# observer.net
KiCad netlist of a schematic drawn in EAGLE
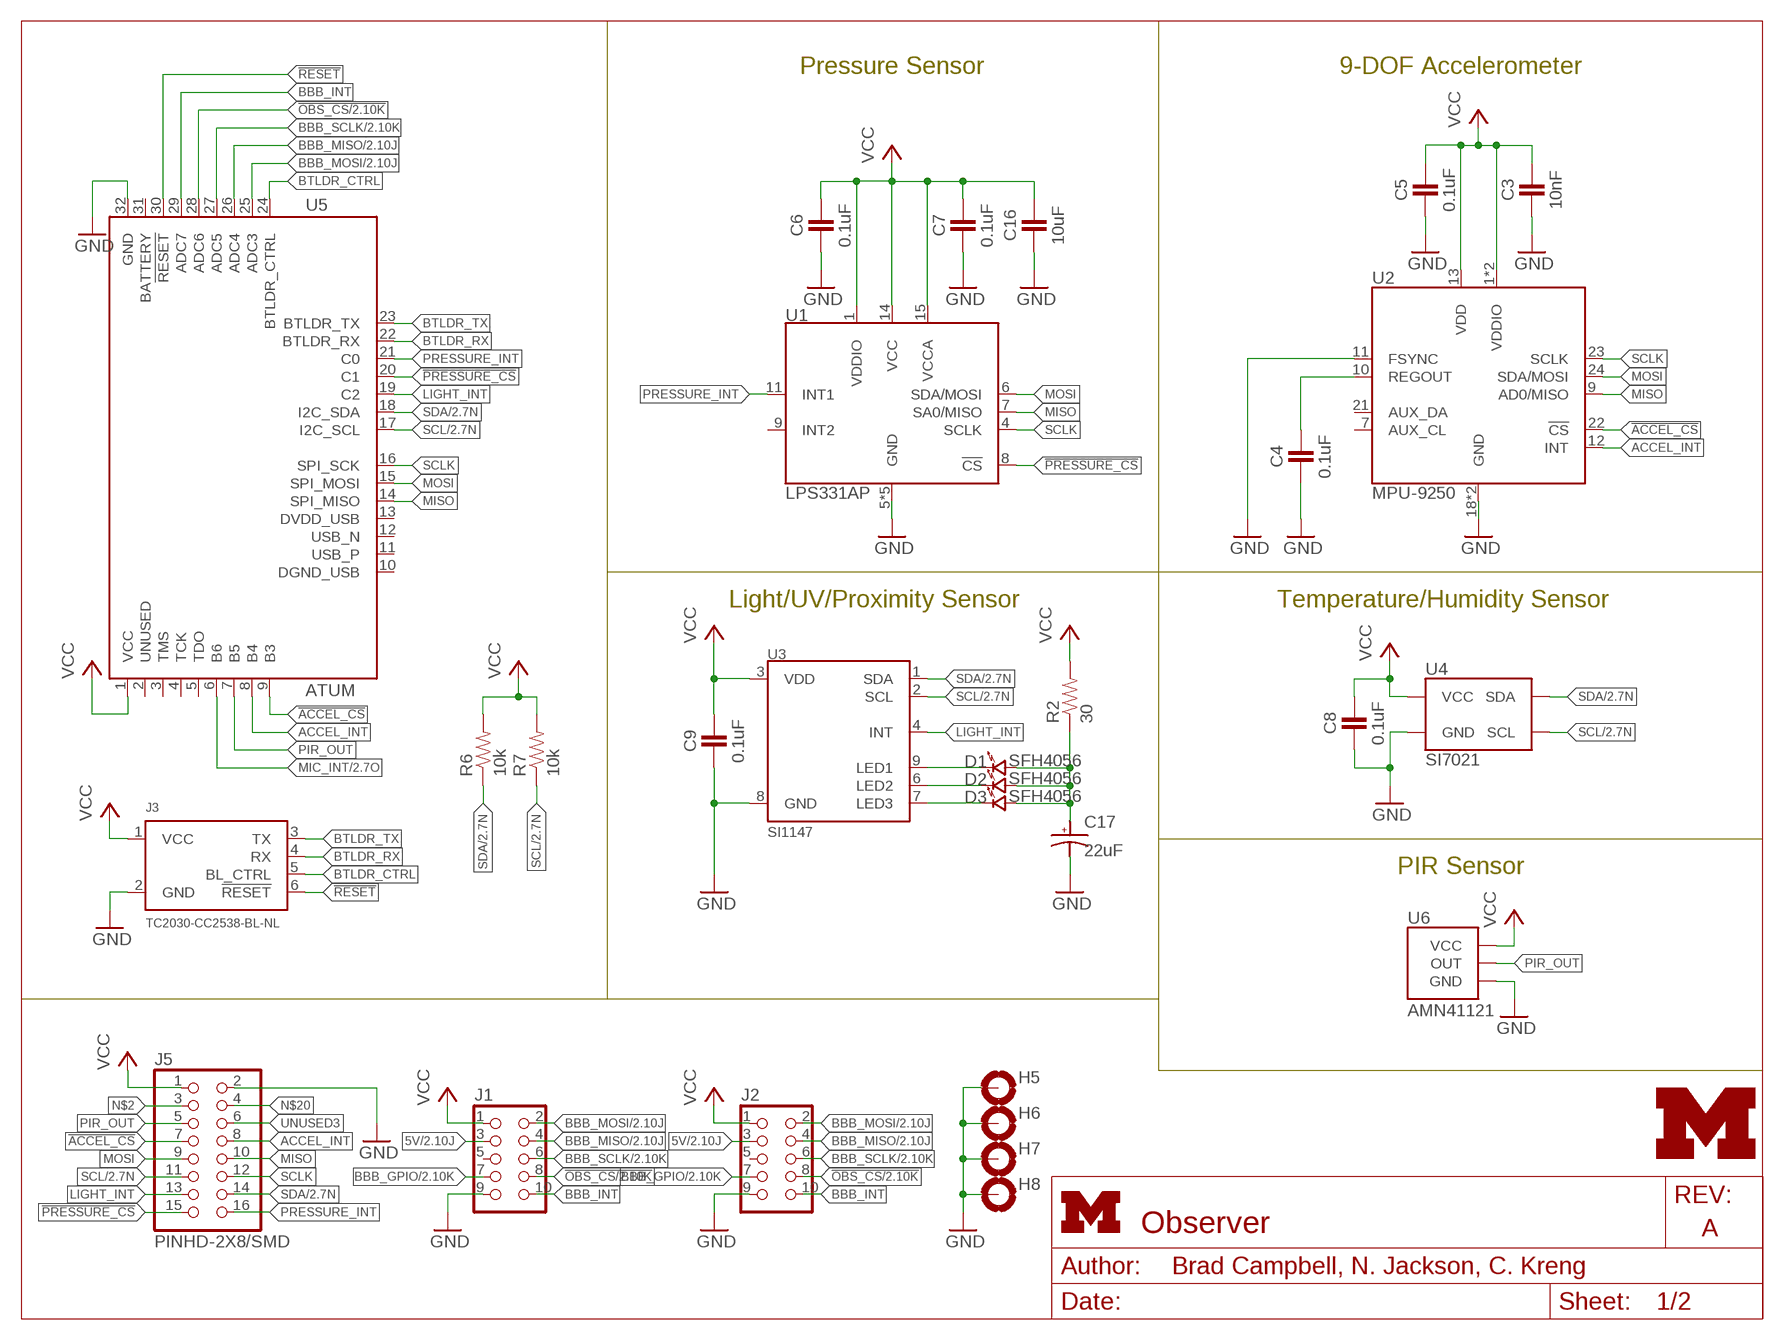
[diagram p0: schematic, sheet 1]
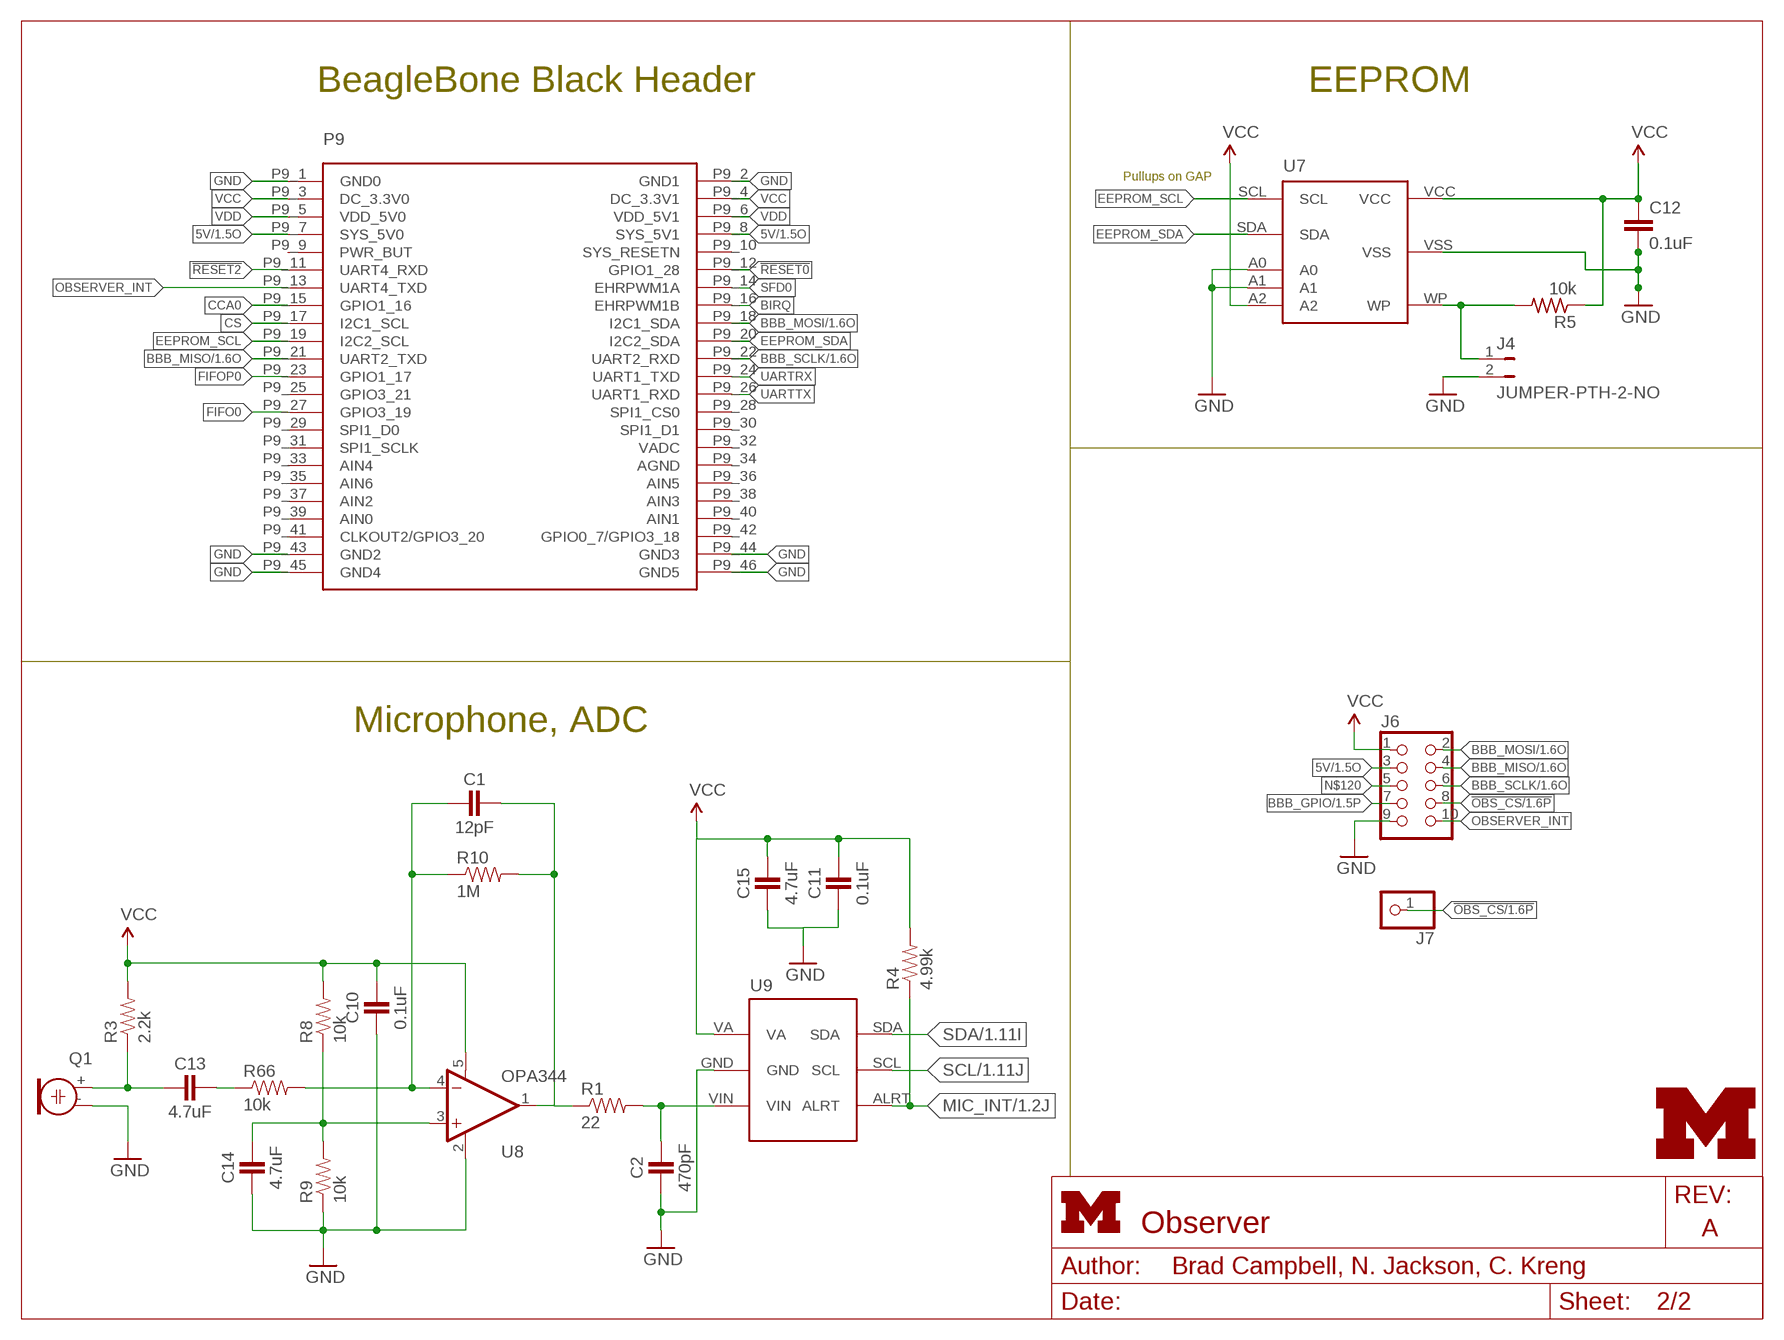
[diagram p1: schematic, sheet 2]

(export (version "E")
  (design (tool "Eeschema 10.0.6"))
  (components
    (comp (ref "C1")
      (value "12pF")
      (footprint "eagle-import:0402_CAP")
      (libsource (lib "eagle-import") (part "CAPACITOR"))
    )
    (comp (ref "C2")
      (value "470pF")
      (footprint "eagle-import:0402_CAP")
      (libsource (lib "eagle-import") (part "CAPACITOR"))
    )
    (comp (ref "C10")
      (value "0.1uF")
      (footprint "eagle-import:0402_CAP")
      (libsource (lib "eagle-import") (part "CAPACITOR"))
    )
    (comp (ref "C11")
      (value "0.1uF")
      (footprint "eagle-import:0402_CAP")
      (libsource (lib "eagle-import") (part "CAPACITOR"))
    )
    (comp (ref "C12")
      (value "0.1uF")
      (footprint "eagle-import:C0402")
      (libsource (lib "eagle-import") (part "C-EUC0402"))
    )
    (comp (ref "C13")
      (value "4.7uF")
      (footprint "eagle-import:0402_CAP")
      (libsource (lib "eagle-import") (part "CAPACITOR"))
    )
    (comp (ref "C14")
      (value "4.7uF")
      (footprint "eagle-import:0402_CAP")
      (libsource (lib "eagle-import") (part "CAPACITOR"))
    )
    (comp (ref "C15")
      (value "4.7uF")
      (footprint "eagle-import:0402_CAP")
      (libsource (lib "eagle-import") (part "CAPACITOR"))
    )
    (comp (ref "J4")
      (value "JUMPER-PTH-2-NO")
      (footprint "eagle-import:PTH-JUMPER-2-NO_NO_SILK")
      (libsource (lib "eagle-import") (part "JUMPER-PTH-2-NO"))
    )
    (comp (ref "J6")
      (value "CON_HEADER_2X05-PTH+SHROUDED_A")
      (footprint "eagle-import:PINSHRD_PTH_2X05")
      (libsource (lib "eagle-import") (part "CON_HEADER_2X05-PTH+SHROUDED_A"))
    )
    (comp (ref "J7")
      (value "PINHD-1X1")
      (footprint "eagle-import:1X01")
      (libsource (lib "eagle-import") (part "PINHD-1X1"))
    )
    (comp (ref "LOGO2")
      (value "UMICH_SOLID_TINY")
      (footprint "eagle-import:UMICH_SOLID_50MIL")
      (libsource (lib "eagle-import") (part "UMICH_SOLID_TINY"))
    )
    (comp (ref "P9/P8")
      (value "BBB_HEADER")
      (footprint "eagle-import:BBB_HEADERS")
      (libsource (lib "eagle-import") (part "BBB_HEADER"))
    )
    (comp (ref "Q1")
      (value "ELECTRET")
      (footprint "eagle-import:ELECTRET_9.7")
      (libsource (lib "eagle-import") (part "ELECTRET"))
    )
    (comp (ref "R1")
      (value "22")
      (footprint "eagle-import:0402_RES")
      (libsource (lib "eagle-import") (part "RESISTOR0402_RES"))
    )
    (comp (ref "R3")
      (value "2.2k")
      (footprint "eagle-import:0402_RES")
      (libsource (lib "eagle-import") (part "RESISTOR0402_RES"))
    )
    (comp (ref "R4")
      (value "4.99k")
      (footprint "eagle-import:0402_RES")
      (libsource (lib "eagle-import") (part "RESISTOR0402_RES"))
    )
    (comp (ref "R5")
      (value "10k")
      (footprint "eagle-import:R0402")
      (libsource (lib "eagle-import") (part "R-US_R0402"))
    )
    (comp (ref "R8")
      (value "10k")
      (footprint "eagle-import:0402_RES")
      (libsource (lib "eagle-import") (part "RESISTOR0402_RES"))
    )
    (comp (ref "R9")
      (value "10k")
      (footprint "eagle-import:0402_RES")
      (libsource (lib "eagle-import") (part "RESISTOR0402_RES"))
    )
    (comp (ref "R10")
      (value "1M")
      (footprint "eagle-import:0402_RES")
      (libsource (lib "eagle-import") (part "RESISTOR0402_RES"))
    )
    (comp (ref "R66")
      (value "10k")
      (footprint "eagle-import:0402_RES")
      (libsource (lib "eagle-import") (part "RESISTOR0402_RES"))
    )
    (comp (ref "U7")
      (value "CAT24C256WI-GT3")
      (footprint "eagle-import:CAT24C256WI-GT3")
      (libsource (lib "eagle-import") (part "CAT24C256WI-GT3"))
    )
    (comp (ref "U8")
      (value "OPA344")
      (footprint "eagle-import:SOT23-5")
      (libsource (lib "eagle-import") (part "OPA344"))
    )
    (comp (ref "U9")
      (value "ADC121C021")
      (footprint "eagle-import:ADC121C021")
      (libsource (lib "eagle-import") (part "ADC121C021"))
    )
    (comp (ref "C3")
      (value "10nF")
      (footprint "eagle-import:0402_CAP")
      (libsource (lib "eagle-import") (part "CAPACITOR"))
    )
    (comp (ref "C4")
      (value "0.1uF")
      (footprint "eagle-import:0402_CAP")
      (libsource (lib "eagle-import") (part "CAPACITOR"))
    )
    (comp (ref "C5")
      (value "0.1uF")
      (footprint "eagle-import:0402_CAP")
      (libsource (lib "eagle-import") (part "CAPACITOR"))
    )
    (comp (ref "C6")
      (value "0.1uF")
      (footprint "eagle-import:0402_CAP")
      (libsource (lib "eagle-import") (part "CAPACITOR"))
    )
    (comp (ref "C7")
      (value "0.1uF")
      (footprint "eagle-import:0402_CAP")
      (libsource (lib "eagle-import") (part "CAPACITOR"))
    )
    (comp (ref "C8")
      (value "0.1uF")
      (footprint "eagle-import:0402_CAP")
      (libsource (lib "eagle-import") (part "CAPACITOR"))
    )
    (comp (ref "C9")
      (value "0.1uF")
      (footprint "eagle-import:0402_CAP")
      (libsource (lib "eagle-import") (part "CAPACITOR"))
    )
    (comp (ref "C16")
      (value "10uF")
      (footprint "eagle-import:0402_CAP")
      (libsource (lib "eagle-import") (part "CAPACITOR"))
    )
    (comp (ref "C17")
      (value "22uF")
      (footprint "eagle-import:CAP0603")
      (libsource (lib "eagle-import") (part "CAP_POL0603"))
    )
    (comp (ref "D1")
      (value "SFH4056")
      (footprint "eagle-import:SFH4056")
      (libsource (lib "eagle-import") (part "SFH4056"))
    )
    (comp (ref "D2")
      (value "SFH4056")
      (footprint "eagle-import:SFH4056")
      (libsource (lib "eagle-import") (part "SFH4056"))
    )
    (comp (ref "D3")
      (value "SFH4056")
      (footprint "eagle-import:SFH4056")
      (libsource (lib "eagle-import") (part "SFH4056"))
    )
    (comp (ref "H5")
      (value "MOUNT-PAD-ROUND3.2")
      (footprint "eagle-import:3,2-PAD")
      (libsource (lib "eagle-import") (part "MOUNT-PAD-ROUND3.2"))
    )
    (comp (ref "H6")
      (value "MOUNT-PAD-ROUND3.2")
      (footprint "eagle-import:3,2-PAD")
      (libsource (lib "eagle-import") (part "MOUNT-PAD-ROUND3.2"))
    )
    (comp (ref "H7")
      (value "MOUNT-PAD-ROUND3.2")
      (footprint "eagle-import:3,2-PAD")
      (libsource (lib "eagle-import") (part "MOUNT-PAD-ROUND3.2"))
    )
    (comp (ref "H8")
      (value "MOUNT-PAD-ROUND3.2")
      (footprint "eagle-import:3,2-PAD")
      (libsource (lib "eagle-import") (part "MOUNT-PAD-ROUND3.2"))
    )
    (comp (ref "J1")
      (value "CON_HEADER_2X05-SMD+SHROUDED")
      (footprint "eagle-import:PINSHRD_SMT_2X05")
      (libsource (lib "eagle-import") (part "CON_HEADER_2X05-SMD+SHROUDED"))
    )
    (comp (ref "J2")
      (value "CON_HEADER_2X05-SMD+SHROUDED")
      (footprint "eagle-import:PINSHRD_SMT_2X05")
      (libsource (lib "eagle-import") (part "CON_HEADER_2X05-SMD+SHROUDED"))
    )
    (comp (ref "J3")
      (value "TC2030-CC2538-BL-NL")
      (footprint "eagle-import:TC2030-IDC-NL")
      (libsource (lib "eagle-import") (part "TC2030-CC2538-BL-NL"))
    )
    (comp (ref "J5")
      (value "PINHD-2X8/SMD")
      (footprint "eagle-import:2X8_SMD")
      (libsource (lib "eagle-import") (part "PINHD-2X8/SMD"))
    )
    (comp (ref "LOGO1")
      (value "UMICH_SOLID_TINY")
      (footprint "eagle-import:UMICH_SOLID_50MIL")
      (libsource (lib "eagle-import") (part "UMICH_SOLID_TINY"))
    )
    (comp (ref "R2")
      (value "30")
      (footprint "eagle-import:0402_RES")
      (libsource (lib "eagle-import") (part "RESISTOR0402_RES"))
    )
    (comp (ref "R6")
      (value "10k")
      (footprint "eagle-import:0402_RES")
      (libsource (lib "eagle-import") (part "RESISTOR0402_RES"))
    )
    (comp (ref "R7")
      (value "10k")
      (footprint "eagle-import:0402_RES")
      (libsource (lib "eagle-import") (part "RESISTOR0402_RES"))
    )
    (comp (ref "U1")
      (value "LPS331AP")
      (footprint "eagle-import:HCLGA-16_3MM")
      (libsource (lib "eagle-import") (part "LPS331AP"))
    )
    (comp (ref "U2")
      (value "MPU-9250")
      (footprint "eagle-import:QFN-24_3MM")
      (libsource (lib "eagle-import") (part "MPU-9250"))
    )
    (comp (ref "U3")
      (value "SI1147")
      (footprint "eagle-import:QFN-10_2MM")
      (libsource (lib "eagle-import") (part "SI1147"))
    )
    (comp (ref "U4")
      (value "SI7021")
      (footprint "eagle-import:DFN-6_3MM")
      (libsource (lib "eagle-import") (part "SI7021"))
    )
    (comp (ref "U5")
      (value "ATUM")
      (footprint "eagle-import:ATUM")
      (libsource (lib "eagle-import") (part "ATUM"))
    )
    (comp (ref "U6")
      (value "AMN41121")
      (footprint "eagle-import:AMN2")
      (libsource (lib "eagle-import") (part "AMN41121"))
    )
  )
  (nets
    (net (code "1") (name "5V") (class "Default")
      (node (ref "J1") (pin "3") (pinfunction "3_3") (pintype "passive"))
      (node (ref "J2") (pin "3") (pinfunction "3_3") (pintype "passive"))
      (node (ref "J6") (pin "3") (pinfunction "3_3") (pintype "passive"))
      (node (ref "P9/P8") (pin "P9_7") (pinfunction "SYS_5V0_P9_7") (pintype "bidirectional"))
      (node (ref "P9/P8") (pin "P9_8") (pinfunction "SYS_5V1_P9_8") (pintype "bidirectional"))
    )
    (net (code "2") (name "ACCEL_INT") (class "Default")
      (node (ref "J5") (pin "8") (pinfunction "8_8") (pintype "passive"))
      (node (ref "U2") (pin "12") (pinfunction "INT_12") (pintype "bidirectional"))
      (node (ref "U5") (pin "8") (pinfunction "B4_8") (pintype "bidirectional"))
    )
    (net (code "3") (name "BBB_GPIO") (class "Default")
      (node (ref "J1") (pin "7") (pinfunction "7_7") (pintype "passive"))
      (node (ref "J2") (pin "7") (pinfunction "7_7") (pintype "passive"))
      (node (ref "J6") (pin "7") (pinfunction "7_7") (pintype "passive"))
    )
    (net (code "4") (name "BBB_INT") (class "Default")
      (node (ref "J1") (pin "10") (pinfunction "10_10") (pintype "passive"))
      (node (ref "J2") (pin "10") (pinfunction "10_10") (pintype "passive"))
      (node (ref "U5") (pin "29") (pinfunction "ADC7_29") (pintype "bidirectional"))
    )
    (net (code "5") (name "BBB_MISO") (class "Default")
      (node (ref "J1") (pin "4") (pinfunction "4_4") (pintype "passive"))
      (node (ref "J2") (pin "4") (pinfunction "4_4") (pintype "passive"))
      (node (ref "J6") (pin "4") (pinfunction "4_4") (pintype "passive"))
      (node (ref "P9/P8") (pin "P9_21") (pinfunction "UART2_TXD_P9_21") (pintype "bidirectional"))
      (node (ref "U5") (pin "26") (pinfunction "ADC4_26") (pintype "bidirectional"))
    )
    (net (code "6") (name "BBB_MOSI") (class "Default")
      (node (ref "J1") (pin "2") (pinfunction "2_2") (pintype "passive"))
      (node (ref "J2") (pin "2") (pinfunction "2_2") (pintype "passive"))
      (node (ref "J6") (pin "2") (pinfunction "2_2") (pintype "passive"))
      (node (ref "P9/P8") (pin "P9_18") (pinfunction "I2C1_SDA_P9_18") (pintype "bidirectional"))
      (node (ref "U5") (pin "25") (pinfunction "ADC3_25") (pintype "bidirectional"))
    )
    (net (code "7") (name "BBB_SCLK") (class "Default")
      (node (ref "J1") (pin "6") (pinfunction "6_6") (pintype "passive"))
      (node (ref "J2") (pin "6") (pinfunction "6_6") (pintype "passive"))
      (node (ref "J6") (pin "6") (pinfunction "6_6") (pintype "passive"))
      (node (ref "P9/P8") (pin "P9_22") (pinfunction "UART2_RXD_P9_22") (pintype "bidirectional"))
      (node (ref "U5") (pin "27") (pinfunction "ADC5_27") (pintype "bidirectional"))
    )
    (net (code "8") (name "BIRQ") (class "Default")
      (node (ref "P9/P8") (pin "P9_16") (pinfunction "EHRPWM1B_P9_16") (pintype "bidirectional"))
    )
    (net (code "9") (name "BTLDR_CTRL") (class "Default")
      (node (ref "J3") (pin "5") (pinfunction "BL_CTRL_5") (pintype "bidirectional"))
      (node (ref "U5") (pin "24") (pinfunction "BTLDR_CTRL_24") (pintype "bidirectional"))
    )
    (net (code "10") (name "BTLDR_RX") (class "Default")
      (node (ref "J3") (pin "4") (pinfunction "RX_4") (pintype "bidirectional"))
      (node (ref "U5") (pin "22") (pinfunction "BTLDR_RX_22") (pintype "bidirectional"))
    )
    (net (code "11") (name "BTLDR_TX") (class "Default")
      (node (ref "J3") (pin "3") (pinfunction "TX_3") (pintype "bidirectional"))
      (node (ref "U5") (pin "23") (pinfunction "BTLDR_TX_23") (pintype "bidirectional"))
    )
    (net (code "12") (name "CCA0") (class "Default")
      (node (ref "P9/P8") (pin "P9_15") (pinfunction "GPIO1_16_P9_15") (pintype "bidirectional"))
    )
    (net (code "13") (name "CS") (class "Default")
      (node (ref "P9/P8") (pin "P9_17") (pinfunction "I2C1_SCL_P9_17") (pintype "bidirectional"))
    )
    (net (code "14") (name "EEPROM_SCL") (class "Default")
      (node (ref "P9/P8") (pin "P9_19") (pinfunction "I2C2_SCL_P9_19") (pintype "bidirectional"))
      (node (ref "U7") (pin "SCL") (pinfunction "SCL_SCL") (pintype "bidirectional"))
    )
    (net (code "15") (name "EEPROM_SDA") (class "Default")
      (node (ref "P9/P8") (pin "P9_20") (pinfunction "I2C2_SDA_P9_20") (pintype "bidirectional"))
      (node (ref "U7") (pin "SDA") (pinfunction "SDA_SDA") (pintype "bidirectional"))
    )
    (net (code "16") (name "FIFO0") (class "Default")
      (node (ref "P9/P8") (pin "P9_27") (pinfunction "GPIO3_19_P9_27") (pintype "bidirectional"))
    )
    (net (code "17") (name "FIFOP0") (class "Default")
      (node (ref "P9/P8") (pin "P9_23") (pinfunction "GPIO1_17_P9_23") (pintype "bidirectional"))
    )
    (net (code "18") (name "GND") (class "Default")
      (node (ref "C10") (pin "2") (pinfunction "2_2") (pintype "bidirectional"))
      (node (ref "C11") (pin "2") (pinfunction "2_2") (pintype "bidirectional"))
      (node (ref "C12") (pin "2") (pinfunction "2_2") (pintype "passive"))
      (node (ref "C14") (pin "2") (pinfunction "2_2") (pintype "bidirectional"))
      (node (ref "C15") (pin "2") (pinfunction "2_2") (pintype "bidirectional"))
      (node (ref "C16") (pin "2") (pinfunction "2_2") (pintype "bidirectional"))
      (node (ref "C17") (pin "NEG") (pinfunction "ANODE_NEG") (pintype "bidirectional"))
      (node (ref "C2") (pin "2") (pinfunction "2_2") (pintype "bidirectional"))
      (node (ref "C3") (pin "2") (pinfunction "2_2") (pintype "bidirectional"))
      (node (ref "C4") (pin "2") (pinfunction "2_2") (pintype "bidirectional"))
      (node (ref "C5") (pin "2") (pinfunction "2_2") (pintype "bidirectional"))
      (node (ref "C6") (pin "2") (pinfunction "2_2") (pintype "bidirectional"))
      (node (ref "C7") (pin "2") (pinfunction "2_2") (pintype "bidirectional"))
      (node (ref "C8") (pin "2") (pinfunction "2_2") (pintype "bidirectional"))
      (node (ref "C9") (pin "2") (pinfunction "2_2") (pintype "bidirectional"))
      (node (ref "H5") (pin "B3,2") (pinfunction "MOUNT_B3,2") (pintype "passive"))
      (node (ref "H6") (pin "B3,2") (pinfunction "MOUNT_B3,2") (pintype "passive"))
      (node (ref "H7") (pin "B3,2") (pinfunction "MOUNT_B3,2") (pintype "passive"))
      (node (ref "H8") (pin "B3,2") (pinfunction "MOUNT_B3,2") (pintype "passive"))
      (node (ref "J1") (pin "9") (pinfunction "9_9") (pintype "passive"))
      (node (ref "J2") (pin "9") (pinfunction "9_9") (pintype "passive"))
      (node (ref "J3") (pin "2") (pinfunction "GND_2") (pintype "bidirectional"))
      (node (ref "J4") (pin "2") (pinfunction "2_2") (pintype "passive"))
      (node (ref "J5") (pin "2") (pinfunction "2_2") (pintype "passive"))
      (node (ref "J6") (pin "9") (pinfunction "9_9") (pintype "passive"))
      (node (ref "P9/P8") (pin "P9_1") (pinfunction "GND0_P9_1") (pintype "bidirectional"))
      (node (ref "P9/P8") (pin "P9_2") (pinfunction "GND1_P9_2") (pintype "bidirectional"))
      (node (ref "P9/P8") (pin "P9_43") (pinfunction "GND2_P9_43") (pintype "bidirectional"))
      (node (ref "P9/P8") (pin "P9_44") (pinfunction "GND3_P9_44") (pintype "bidirectional"))
      (node (ref "P9/P8") (pin "P9_45") (pinfunction "GND4_P9_45") (pintype "bidirectional"))
      (node (ref "P9/P8") (pin "P9_46") (pinfunction "GND5_P9_46") (pintype "bidirectional"))
      (node (ref "Q1") (pin "-") (pinfunction "1_-") (pintype "passive"))
      (node (ref "R9") (pin "1") (pinfunction "1_1") (pintype "passive"))
      (node (ref "U1") (pin "10") (pinfunction "GND_10") (pintype "bidirectional"))
      (node (ref "U1") (pin "12") (pinfunction "GND_12") (pintype "bidirectional"))
      (node (ref "U1") (pin "13") (pinfunction "GND_13") (pintype "bidirectional"))
      (node (ref "U1") (pin "16") (pinfunction "GND_16") (pintype "bidirectional"))
      (node (ref "U1") (pin "5") (pinfunction "GND_5") (pintype "bidirectional"))
      (node (ref "U2") (pin "11") (pinfunction "FSYNC_11") (pintype "bidirectional"))
      (node (ref "U2") (pin "18") (pinfunction "GND_18") (pintype "bidirectional"))
      (node (ref "U2") (pin "20") (pinfunction "GND_20") (pintype "bidirectional"))
      (node (ref "U3") (pin "8") (pinfunction "GND_8") (pintype "bidirectional"))
      (node (ref "U4") (pin "2") (pinfunction "GND_2") (pintype "bidirectional"))
      (node (ref "U5") (pin "32") (pinfunction "GND_32") (pintype "bidirectional"))
      (node (ref "U6") (pin "GND") (pinfunction "GND_GND") (pintype "bidirectional"))
      (node (ref "U7") (pin "A0") (pinfunction "A0_A0") (pintype "bidirectional"))
      (node (ref "U7") (pin "A1") (pinfunction "A1_A1") (pintype "bidirectional"))
      (node (ref "U7") (pin "VSS") (pinfunction "VSS_VSS") (pintype "bidirectional"))
      (node (ref "U8") (pin "2") (pinfunction "V-_2") (pintype "power_in"))
      (node (ref "U9") (pin "GND") (pinfunction "GND_GND") (pintype "bidirectional"))
    )
    (net (code "19") (name "LIGHT_INT") (class "Default")
      (node (ref "J5") (pin "13") (pinfunction "13_13") (pintype "passive"))
      (node (ref "U3") (pin "4") (pinfunction "INT_4") (pintype "bidirectional"))
      (node (ref "U5") (pin "19") (pinfunction "C2_19") (pintype "bidirectional"))
    )
    (net (code "20") (name "MIC_INT") (class "Default")
      (node (ref "R4") (pin "1") (pinfunction "1_1") (pintype "passive"))
      (node (ref "U5") (pin "6") (pinfunction "B6_6") (pintype "bidirectional"))
      (node (ref "U9") (pin "ALRT") (pinfunction "ALRT_ALRT") (pintype "bidirectional"))
    )
    (net (code "21") (name "MISO") (class "Default")
      (node (ref "J5") (pin "10") (pinfunction "10_10") (pintype "passive"))
      (node (ref "U1") (pin "7") (pinfunction "SA0/MISO_7") (pintype "bidirectional"))
      (node (ref "U2") (pin "9") (pinfunction "AD0/MISO_9") (pintype "bidirectional"))
      (node (ref "U5") (pin "14") (pinfunction "SPI_MISO_14") (pintype "bidirectional"))
    )
    (net (code "22") (name "MOSI") (class "Default")
      (node (ref "J5") (pin "9") (pinfunction "9_9") (pintype "passive"))
      (node (ref "U1") (pin "6") (pinfunction "SDA/MOSI_6") (pintype "bidirectional"))
      (node (ref "U2") (pin "24") (pinfunction "SDA/MOSI_24") (pintype "bidirectional"))
      (node (ref "U5") (pin "15") (pinfunction "SPI_MOSI_15") (pintype "bidirectional"))
    )
    (net (code "23") (name "N$2") (class "Default")
      (node (ref "J5") (pin "3") (pinfunction "3_3") (pintype "passive"))
    )
    (net (code "24") (name "N$20") (class "Default")
      (node (ref "J5") (pin "4") (pinfunction "4_4") (pintype "passive"))
    )
    (net (code "25") (name "N$120") (class "Default")
      (node (ref "J6") (pin "5") (pinfunction "5_5") (pintype "passive"))
    )
    (net (code "26") (name "Net-(C2-Pad1)") (class "Default")
      (node (ref "C2") (pin "1") (pinfunction "1_1") (pintype "bidirectional"))
      (node (ref "R1") (pin "2") (pinfunction "2_2") (pintype "passive"))
      (node (ref "U9") (pin "VIN") (pinfunction "VIN_VIN") (pintype "bidirectional"))
    )
    (net (code "27") (name "Net-(C13-Pad1)") (class "Default")
      (node (ref "C13") (pin "1") (pinfunction "1_1") (pintype "bidirectional"))
      (node (ref "R66") (pin "1") (pinfunction "1_1") (pintype "passive"))
    )
    (net (code "28") (name "Net-(C17-CATHODE)") (class "Default")
      (node (ref "C17") (pin "POS") (pinfunction "CATHODE_POS") (pintype "bidirectional"))
      (node (ref "D1") (pin "ANODE") (pinfunction "ANODE_ANODE") (pintype "bidirectional"))
      (node (ref "D2") (pin "ANODE") (pinfunction "ANODE_ANODE") (pintype "bidirectional"))
      (node (ref "D3") (pin "ANODE") (pinfunction "ANODE_ANODE") (pintype "bidirectional"))
      (node (ref "R2") (pin "1") (pinfunction "1_1") (pintype "passive"))
    )
    (net (code "29") (name "Net-(J4-Pad1)") (class "Default")
      (node (ref "J4") (pin "1") (pinfunction "1_1") (pintype "passive"))
      (node (ref "R5") (pin "2") (pinfunction "2_2") (pintype "passive"))
      (node (ref "U7") (pin "WP") (pinfunction "WP_WP") (pintype "bidirectional"))
    )
    (net (code "30") (name "Net-(Q1-2)") (class "Default")
      (node (ref "C13") (pin "2") (pinfunction "2_2") (pintype "bidirectional"))
      (node (ref "Q1") (pin "+") (pinfunction "2_+") (pintype "passive"))
      (node (ref "R3") (pin "1") (pinfunction "1_1") (pintype "passive"))
    )
    (net (code "31") (name "Net-(U2-REGOUT)") (class "Default")
      (node (ref "C4") (pin "1") (pinfunction "1_1") (pintype "bidirectional"))
      (node (ref "U2") (pin "10") (pinfunction "REGOUT_10") (pintype "bidirectional"))
    )
    (net (code "32") (name "Net-(U3-LED1)") (class "Default")
      (node (ref "D1") (pin "CATHODE") (pinfunction "CATHODE_CATHODE") (pintype "bidirectional"))
      (node (ref "U3") (pin "9") (pinfunction "LED1_9") (pintype "bidirectional"))
    )
    (net (code "33") (name "Net-(U3-LED2)") (class "Default")
      (node (ref "D2") (pin "CATHODE") (pinfunction "CATHODE_CATHODE") (pintype "bidirectional"))
      (node (ref "U3") (pin "6") (pinfunction "LED2_6") (pintype "bidirectional"))
    )
    (net (code "34") (name "Net-(U3-LED3)") (class "Default")
      (node (ref "D3") (pin "CATHODE") (pinfunction "CATHODE_CATHODE") (pintype "bidirectional"))
      (node (ref "U3") (pin "7") (pinfunction "LED3_7") (pintype "bidirectional"))
    )
    (net (code "35") (name "Net-(U8-+IN)") (class "Default")
      (node (ref "C14") (pin "1") (pinfunction "1_1") (pintype "bidirectional"))
      (node (ref "R8") (pin "1") (pinfunction "1_1") (pintype "passive"))
      (node (ref "R9") (pin "2") (pinfunction "2_2") (pintype "passive"))
      (node (ref "U8") (pin "3") (pinfunction "+IN_3") (pintype "input"))
    )
    (net (code "36") (name "Net-(U8--IN)") (class "Default")
      (node (ref "C1") (pin "2") (pinfunction "2_2") (pintype "bidirectional"))
      (node (ref "R10") (pin "1") (pinfunction "1_1") (pintype "passive"))
      (node (ref "R66") (pin "2") (pinfunction "2_2") (pintype "passive"))
      (node (ref "U8") (pin "4") (pinfunction "-IN_4") (pintype "input"))
    )
    (net (code "37") (name "Net-(U8-OUT)") (class "Default")
      (node (ref "C1") (pin "1") (pinfunction "1_1") (pintype "bidirectional"))
      (node (ref "R1") (pin "1") (pinfunction "1_1") (pintype "passive"))
      (node (ref "R10") (pin "2") (pinfunction "2_2") (pintype "passive"))
      (node (ref "U8") (pin "1") (pinfunction "OUT_1") (pintype "output"))
    )
    (net (code "38") (name "OBSERVER_INT") (class "Default")
      (node (ref "J6") (pin "10") (pinfunction "10_10") (pintype "passive"))
      (node (ref "P9/P8") (pin "P9_13") (pinfunction "UART4_TXD_P9_13") (pintype "bidirectional"))
    )
    (net (code "39") (name "PIR_OUT") (class "Default")
      (node (ref "J5") (pin "5") (pinfunction "5_5") (pintype "passive"))
      (node (ref "U5") (pin "7") (pinfunction "B5_7") (pintype "bidirectional"))
      (node (ref "U6") (pin "OUT") (pinfunction "OUT_OUT") (pintype "bidirectional"))
    )
    (net (code "40") (name "PRESSURE_INT") (class "Default")
      (node (ref "J5") (pin "16") (pinfunction "16_16") (pintype "passive"))
      (node (ref "U1") (pin "11") (pinfunction "INT1_11") (pintype "bidirectional"))
      (node (ref "U5") (pin "21") (pinfunction "C0_21") (pintype "bidirectional"))
    )
    (net (code "41") (name "SCL") (class "Default")
      (node (ref "J5") (pin "11") (pinfunction "11_11") (pintype "passive"))
      (node (ref "R7") (pin "1") (pinfunction "1_1") (pintype "passive"))
      (node (ref "U3") (pin "2") (pinfunction "SCL_2") (pintype "bidirectional"))
      (node (ref "U4") (pin "6") (pinfunction "SCL_6") (pintype "bidirectional"))
      (node (ref "U5") (pin "17") (pinfunction "I2C_SCL_17") (pintype "bidirectional"))
      (node (ref "U9") (pin "SCL") (pinfunction "SCL_SCL") (pintype "bidirectional"))
    )
    (net (code "42") (name "SCLK") (class "Default")
      (node (ref "J5") (pin "12") (pinfunction "12_12") (pintype "passive"))
      (node (ref "U1") (pin "4") (pinfunction "SCLK_4") (pintype "bidirectional"))
      (node (ref "U2") (pin "23") (pinfunction "SCLK_23") (pintype "bidirectional"))
      (node (ref "U5") (pin "16") (pinfunction "SPI_SCK_16") (pintype "bidirectional"))
    )
    (net (code "43") (name "SDA") (class "Default")
      (node (ref "J5") (pin "14") (pinfunction "14_14") (pintype "passive"))
      (node (ref "R6") (pin "1") (pinfunction "1_1") (pintype "passive"))
      (node (ref "U3") (pin "1") (pinfunction "SDA_1") (pintype "bidirectional"))
      (node (ref "U4") (pin "1") (pinfunction "SDA_1") (pintype "bidirectional"))
      (node (ref "U5") (pin "18") (pinfunction "I2C_SDA_18") (pintype "bidirectional"))
      (node (ref "U9") (pin "SDA") (pinfunction "SDA_SDA") (pintype "bidirectional"))
    )
    (net (code "44") (name "SFD0") (class "Default")
      (node (ref "P9/P8") (pin "P9_14") (pinfunction "EHRPWM1A_P9_14") (pintype "bidirectional"))
    )
    (net (code "45") (name "UARTRX") (class "Default")
      (node (ref "P9/P8") (pin "P9_24") (pinfunction "UART1_TXD_P9_24") (pintype "bidirectional"))
    )
    (net (code "46") (name "UARTTX") (class "Default")
      (node (ref "P9/P8") (pin "P9_26") (pinfunction "UART1_RXD_P9_26") (pintype "bidirectional"))
    )
    (net (code "47") (name "UNUSED3") (class "Default")
      (node (ref "J5") (pin "6") (pinfunction "6_6") (pintype "passive"))
    )
    (net (code "48") (name "VCC") (class "Default")
      (node (ref "C10") (pin "1") (pinfunction "1_1") (pintype "bidirectional"))
      (node (ref "C11") (pin "1") (pinfunction "1_1") (pintype "bidirectional"))
      (node (ref "C12") (pin "1") (pinfunction "1_1") (pintype "passive"))
      (node (ref "C15") (pin "1") (pinfunction "1_1") (pintype "bidirectional"))
      (node (ref "C16") (pin "1") (pinfunction "1_1") (pintype "bidirectional"))
      (node (ref "C3") (pin "1") (pinfunction "1_1") (pintype "bidirectional"))
      (node (ref "C5") (pin "1") (pinfunction "1_1") (pintype "bidirectional"))
      (node (ref "C6") (pin "1") (pinfunction "1_1") (pintype "bidirectional"))
      (node (ref "C7") (pin "1") (pinfunction "1_1") (pintype "bidirectional"))
      (node (ref "C8") (pin "1") (pinfunction "1_1") (pintype "bidirectional"))
      (node (ref "C9") (pin "1") (pinfunction "1_1") (pintype "bidirectional"))
      (node (ref "J1") (pin "1") (pinfunction "1_1") (pintype "passive"))
      (node (ref "J2") (pin "1") (pinfunction "1_1") (pintype "passive"))
      (node (ref "J3") (pin "1") (pinfunction "VCC_1") (pintype "bidirectional"))
      (node (ref "J5") (pin "1") (pinfunction "1_1") (pintype "passive"))
      (node (ref "J6") (pin "1") (pinfunction "1_1") (pintype "passive"))
      (node (ref "P9/P8") (pin "P9_3") (pinfunction "DC_3.3V0_P9_3") (pintype "bidirectional"))
      (node (ref "P9/P8") (pin "P9_4") (pinfunction "DC_3.3V1_P9_4") (pintype "bidirectional"))
      (node (ref "R2") (pin "2") (pinfunction "2_2") (pintype "passive"))
      (node (ref "R3") (pin "2") (pinfunction "2_2") (pintype "passive"))
      (node (ref "R4") (pin "2") (pinfunction "2_2") (pintype "passive"))
      (node (ref "R5") (pin "1") (pinfunction "1_1") (pintype "passive"))
      (node (ref "R6") (pin "2") (pinfunction "2_2") (pintype "passive"))
      (node (ref "R7") (pin "2") (pinfunction "2_2") (pintype "passive"))
      (node (ref "R8") (pin "2") (pinfunction "2_2") (pintype "passive"))
      (node (ref "U1") (pin "1") (pinfunction "VDDIO_1") (pintype "bidirectional"))
      (node (ref "U1") (pin "14") (pinfunction "VCC_14") (pintype "bidirectional"))
      (node (ref "U1") (pin "15") (pinfunction "VCCA_15") (pintype "bidirectional"))
      (node (ref "U2") (pin "1") (pinfunction "VDDIO_1") (pintype "bidirectional"))
      (node (ref "U2") (pin "13") (pinfunction "VDD_13") (pintype "bidirectional"))
      (node (ref "U2") (pin "8") (pinfunction "VDDIO_8") (pintype "bidirectional"))
      (node (ref "U3") (pin "3") (pinfunction "VDD_3") (pintype "bidirectional"))
      (node (ref "U4") (pin "5") (pinfunction "VCC_5") (pintype "bidirectional"))
      (node (ref "U5") (pin "1") (pinfunction "VCC_1") (pintype "bidirectional"))
      (node (ref "U6") (pin "VCC") (pinfunction "VCC_VCC") (pintype "bidirectional"))
      (node (ref "U7") (pin "A2") (pinfunction "A2_A2") (pintype "bidirectional"))
      (node (ref "U7") (pin "VCC") (pinfunction "VCC_VCC") (pintype "bidirectional"))
      (node (ref "U8") (pin "5") (pinfunction "V+_5") (pintype "power_in"))
      (node (ref "U9") (pin "VA") (pinfunction "VA_VA") (pintype "bidirectional"))
    )
    (net (code "49") (name "VDD") (class "Default")
      (node (ref "P9/P8") (pin "P9_5") (pinfunction "VDD_5V0_P9_5") (pintype "bidirectional"))
      (node (ref "P9/P8") (pin "P9_6") (pinfunction "VDD_5V1_P9_6") (pintype "bidirectional"))
    )
    (net (code "50") (name "unconnected-(J1-Pad5)") (class "Default")
      (node (ref "J1") (pin "5") (pinfunction "5_5") (pintype "passive"))
    )
    (net (code "51") (name "unconnected-(J2-Pad5)") (class "Default")
      (node (ref "J2") (pin "5") (pinfunction "5_5") (pintype "passive"))
    )
    (net (code "52") (name "unconnected-(P9/P8-AGND-PadP9_34)") (class "Default")
      (node (ref "P9/P8") (pin "P9_34") (pinfunction "AGND_P9_34") (pintype "bidirectional"))
    )
    (net (code "53") (name "unconnected-(P9/P8-AIN0-PadP9_39)") (class "Default")
      (node (ref "P9/P8") (pin "P9_39") (pinfunction "AIN0_P9_39") (pintype "bidirectional"))
    )
    (net (code "54") (name "unconnected-(P9/P8-AIN1-PadP9_40)") (class "Default")
      (node (ref "P9/P8") (pin "P9_40") (pinfunction "AIN1_P9_40") (pintype "bidirectional"))
    )
    (net (code "55") (name "unconnected-(P9/P8-AIN2-PadP9_37)") (class "Default")
      (node (ref "P9/P8") (pin "P9_37") (pinfunction "AIN2_P9_37") (pintype "bidirectional"))
    )
    (net (code "56") (name "unconnected-(P9/P8-AIN3-PadP9_38)") (class "Default")
      (node (ref "P9/P8") (pin "P9_38") (pinfunction "AIN3_P9_38") (pintype "bidirectional"))
    )
    (net (code "57") (name "unconnected-(P9/P8-AIN4-PadP9_33)") (class "Default")
      (node (ref "P9/P8") (pin "P9_33") (pinfunction "AIN4_P9_33") (pintype "bidirectional"))
    )
    (net (code "58") (name "unconnected-(P9/P8-AIN5-PadP9_36)") (class "Default")
      (node (ref "P9/P8") (pin "P9_36") (pinfunction "AIN5_P9_36") (pintype "bidirectional"))
    )
    (net (code "59") (name "unconnected-(P9/P8-AIN6-PadP9_35)") (class "Default")
      (node (ref "P9/P8") (pin "P9_35") (pinfunction "AIN6_P9_35") (pintype "bidirectional"))
    )
    (net (code "60") (name "unconnected-(P9/P8-CLKOUT2{slash}GPIO3_20-PadP9_41)") (class "Default")
      (node (ref "P9/P8") (pin "P9_41") (pinfunction "CLKOUT2/GPIO3_20_P9_41") (pintype "bidirectional"))
    )
    (net (code "61") (name "unconnected-(P9/P8-GPIO0_7{slash}GPIO3_18-PadP9_42)") (class "Default")
      (node (ref "P9/P8") (pin "P9_42") (pinfunction "GPIO0_7/GPIO3_18_P9_42") (pintype "bidirectional"))
    )
    (net (code "62") (name "unconnected-(P9/P8-GPIO3_21-PadP9_25)") (class "Default")
      (node (ref "P9/P8") (pin "P9_25") (pinfunction "GPIO3_21_P9_25") (pintype "bidirectional"))
    )
    (net (code "63") (name "unconnected-(P9/P8-PWR_BUT-PadP9_9)") (class "Default")
      (node (ref "P9/P8") (pin "P9_9") (pinfunction "PWR_BUT_P9_9") (pintype "bidirectional"))
    )
    (net (code "64") (name "unconnected-(P9/P8-SPI1_CS0-PadP9_28)") (class "Default")
      (node (ref "P9/P8") (pin "P9_28") (pinfunction "SPI1_CS0_P9_28") (pintype "bidirectional"))
    )
    (net (code "65") (name "unconnected-(P9/P8-SPI1_D0-PadP9_29)") (class "Default")
      (node (ref "P9/P8") (pin "P9_29") (pinfunction "SPI1_D0_P9_29") (pintype "bidirectional"))
    )
    (net (code "66") (name "unconnected-(P9/P8-SPI1_D1-PadP9_30)") (class "Default")
      (node (ref "P9/P8") (pin "P9_30") (pinfunction "SPI1_D1_P9_30") (pintype "bidirectional"))
    )
    (net (code "67") (name "unconnected-(P9/P8-SPI1_SCLK-PadP9_31)") (class "Default")
      (node (ref "P9/P8") (pin "P9_31") (pinfunction "SPI1_SCLK_P9_31") (pintype "bidirectional"))
    )
    (net (code "68") (name "unconnected-(P9/P8-SYS_RESETN-PadP9_10)") (class "Default")
      (node (ref "P9/P8") (pin "P9_10") (pinfunction "SYS_RESETN_P9_10") (pintype "bidirectional"))
    )
    (net (code "69") (name "unconnected-(P9/P8-VADC-PadP9_32)") (class "Default")
      (node (ref "P9/P8") (pin "P9_32") (pinfunction "VADC_P9_32") (pintype "bidirectional"))
    )
    (net (code "70") (name "unconnected-(U1-INT2-Pad9)") (class "Default")
      (node (ref "U1") (pin "9") (pinfunction "INT2_9") (pintype "bidirectional"))
    )
    (net (code "71") (name "unconnected-(U2-AUX_CL-Pad7)") (class "Default")
      (node (ref "U2") (pin "7") (pinfunction "AUX_CL_7") (pintype "bidirectional"))
    )
    (net (code "72") (name "unconnected-(U2-AUX_DA-Pad21)") (class "Default")
      (node (ref "U2") (pin "21") (pinfunction "AUX_DA_21") (pintype "bidirectional"))
    )
    (net (code "73") (name "unconnected-(U5-BATTERY-Pad31)") (class "Default")
      (node (ref "U5") (pin "31") (pinfunction "BATTERY_31") (pintype "bidirectional"))
    )
    (net (code "74") (name "unconnected-(U5-DGND_USB-Pad10)") (class "Default")
      (node (ref "U5") (pin "10") (pinfunction "DGND_USB_10") (pintype "bidirectional"))
    )
    (net (code "75") (name "unconnected-(U5-DVDD_USB-Pad13)") (class "Default")
      (node (ref "U5") (pin "13") (pinfunction "DVDD_USB_13") (pintype "bidirectional"))
    )
    (net (code "76") (name "unconnected-(U5-TCK-Pad4)") (class "Default")
      (node (ref "U5") (pin "4") (pinfunction "TCK_4") (pintype "bidirectional"))
    )
    (net (code "77") (name "unconnected-(U5-TDO-Pad5)") (class "Default")
      (node (ref "U5") (pin "5") (pinfunction "TDO_5") (pintype "bidirectional"))
    )
    (net (code "78") (name "unconnected-(U5-TMS-Pad3)") (class "Default")
      (node (ref "U5") (pin "3") (pinfunction "TMS_3") (pintype "bidirectional"))
    )
    (net (code "79") (name "unconnected-(U5-UNUSED-Pad2)") (class "Default")
      (node (ref "U5") (pin "2") (pinfunction "UNUSED_2") (pintype "bidirectional"))
    )
    (net (code "80") (name "unconnected-(U5-USB_N-Pad12)") (class "Default")
      (node (ref "U5") (pin "12") (pinfunction "USB_N_12") (pintype "bidirectional"))
    )
    (net (code "81") (name "unconnected-(U5-USB_P-Pad11)") (class "Default")
      (node (ref "U5") (pin "11") (pinfunction "USB_P_11") (pintype "bidirectional"))
    )
    (net (code "82") (name "~{ACCEL_CS}") (class "Default")
      (node (ref "J5") (pin "7") (pinfunction "7_7") (pintype "passive"))
      (node (ref "U2") (pin "22") (pinfunction "~{CS}_22") (pintype "bidirectional"))
      (node (ref "U5") (pin "9") (pinfunction "B3_9") (pintype "bidirectional"))
    )
    (net (code "83") (name "~{OBS_CS}") (class "Default")
      (node (ref "J1") (pin "8") (pinfunction "8_8") (pintype "passive"))
      (node (ref "J2") (pin "8") (pinfunction "8_8") (pintype "passive"))
      (node (ref "J6") (pin "8") (pinfunction "8_8") (pintype "passive"))
      (node (ref "J7") (pin "1") (pinfunction "1_1") (pintype "passive"))
      (node (ref "U5") (pin "28") (pinfunction "ADC6_28") (pintype "bidirectional"))
    )
    (net (code "84") (name "~{PRESSURE_CS}") (class "Default")
      (node (ref "J5") (pin "15") (pinfunction "15_15") (pintype "passive"))
      (node (ref "U1") (pin "8") (pinfunction "~{CS}_8") (pintype "bidirectional"))
      (node (ref "U5") (pin "20") (pinfunction "C1_20") (pintype "bidirectional"))
    )
    (net (code "85") (name "~{RESET0}") (class "Default")
      (node (ref "P9/P8") (pin "P9_12") (pinfunction "GPIO1_28_P9_12") (pintype "bidirectional"))
    )
    (net (code "86") (name "~{RESET2}") (class "Default")
      (node (ref "P9/P8") (pin "P9_11") (pinfunction "UART4_RXD_P9_11") (pintype "bidirectional"))
    )
    (net (code "87") (name "~{RESET}") (class "Default")
      (node (ref "J3") (pin "6") (pinfunction "~{RESET}_6") (pintype "bidirectional"))
      (node (ref "U5") (pin "30") (pinfunction "~{RESET}_30") (pintype "bidirectional"))
    )
  )
)
